# motor_controller.net
KiCad netlist of a schematic drawn in EAGLE
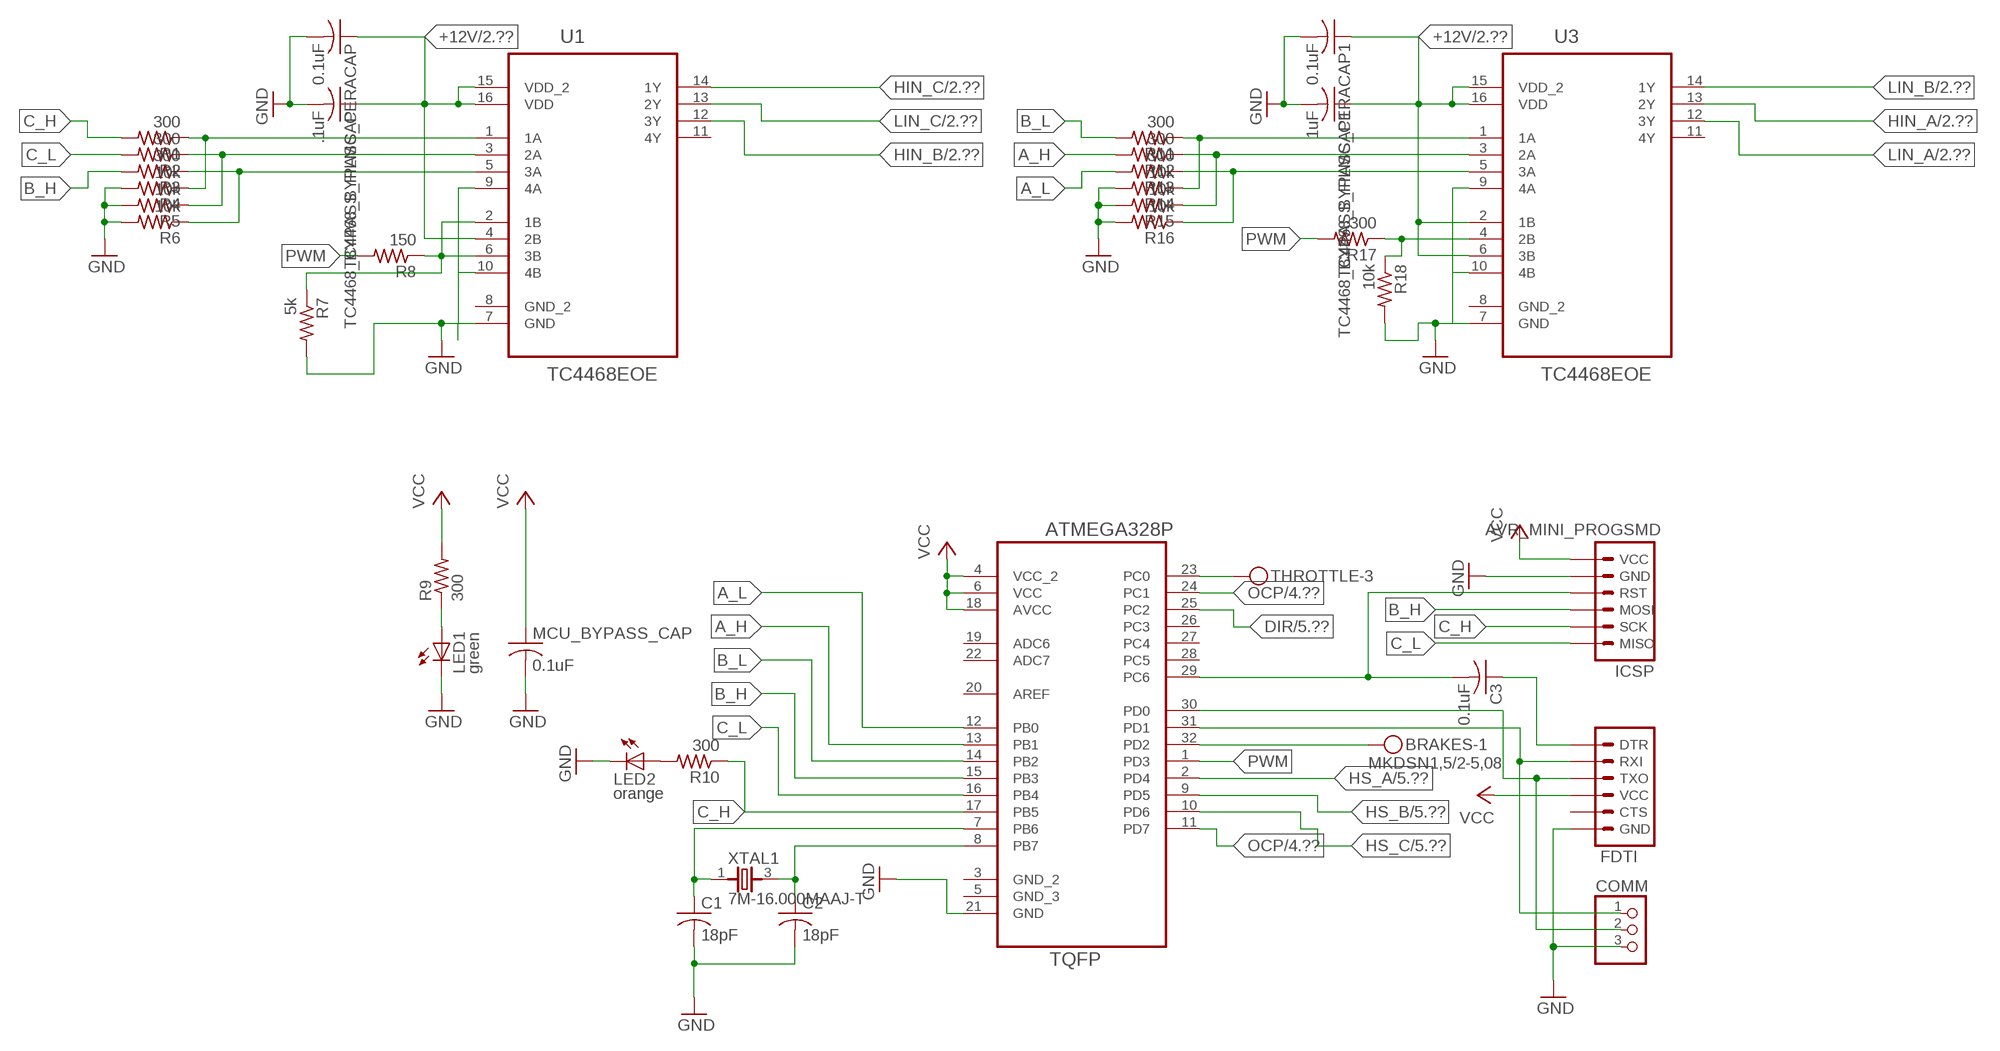
[diagram p0: schematic, sheet 1]
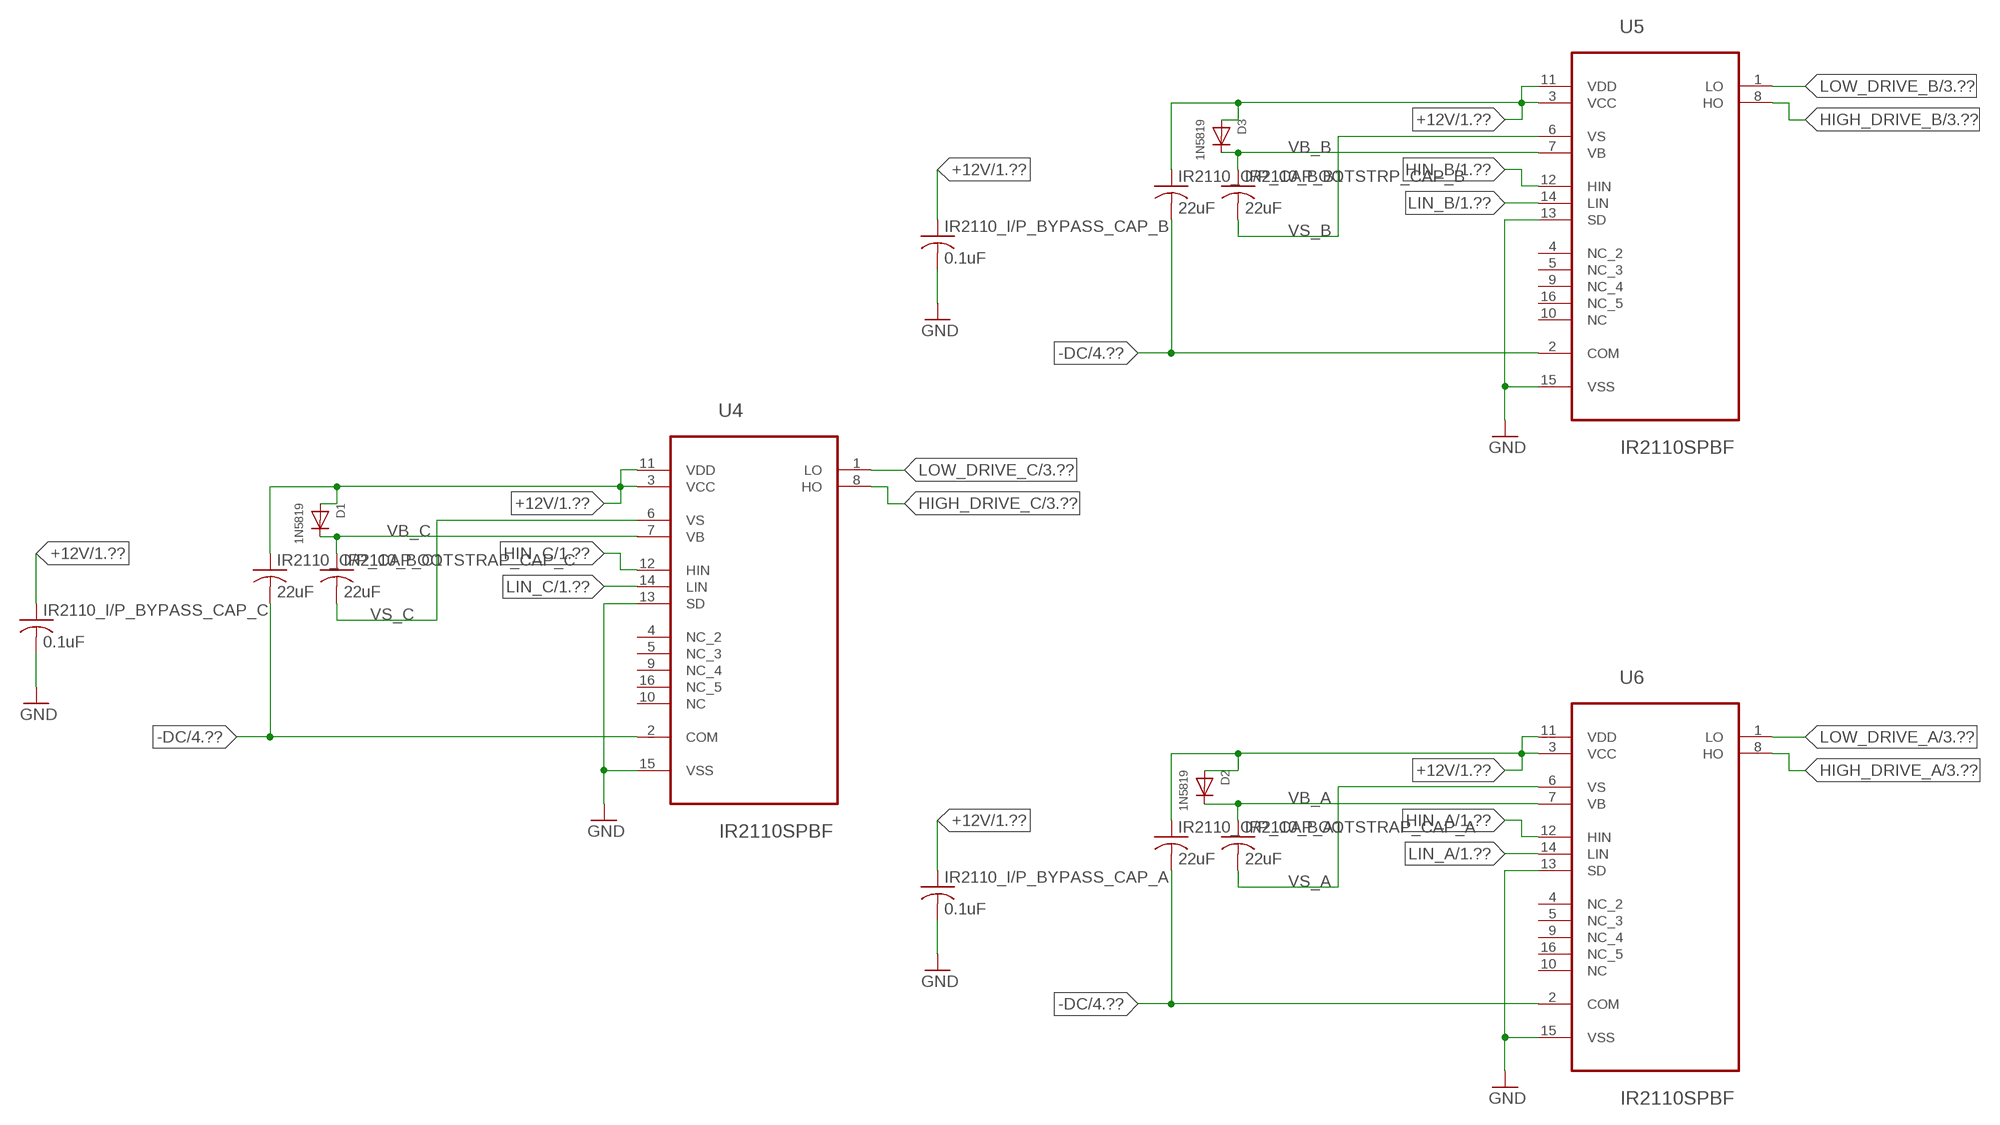
[diagram p1: schematic, sheet 2]
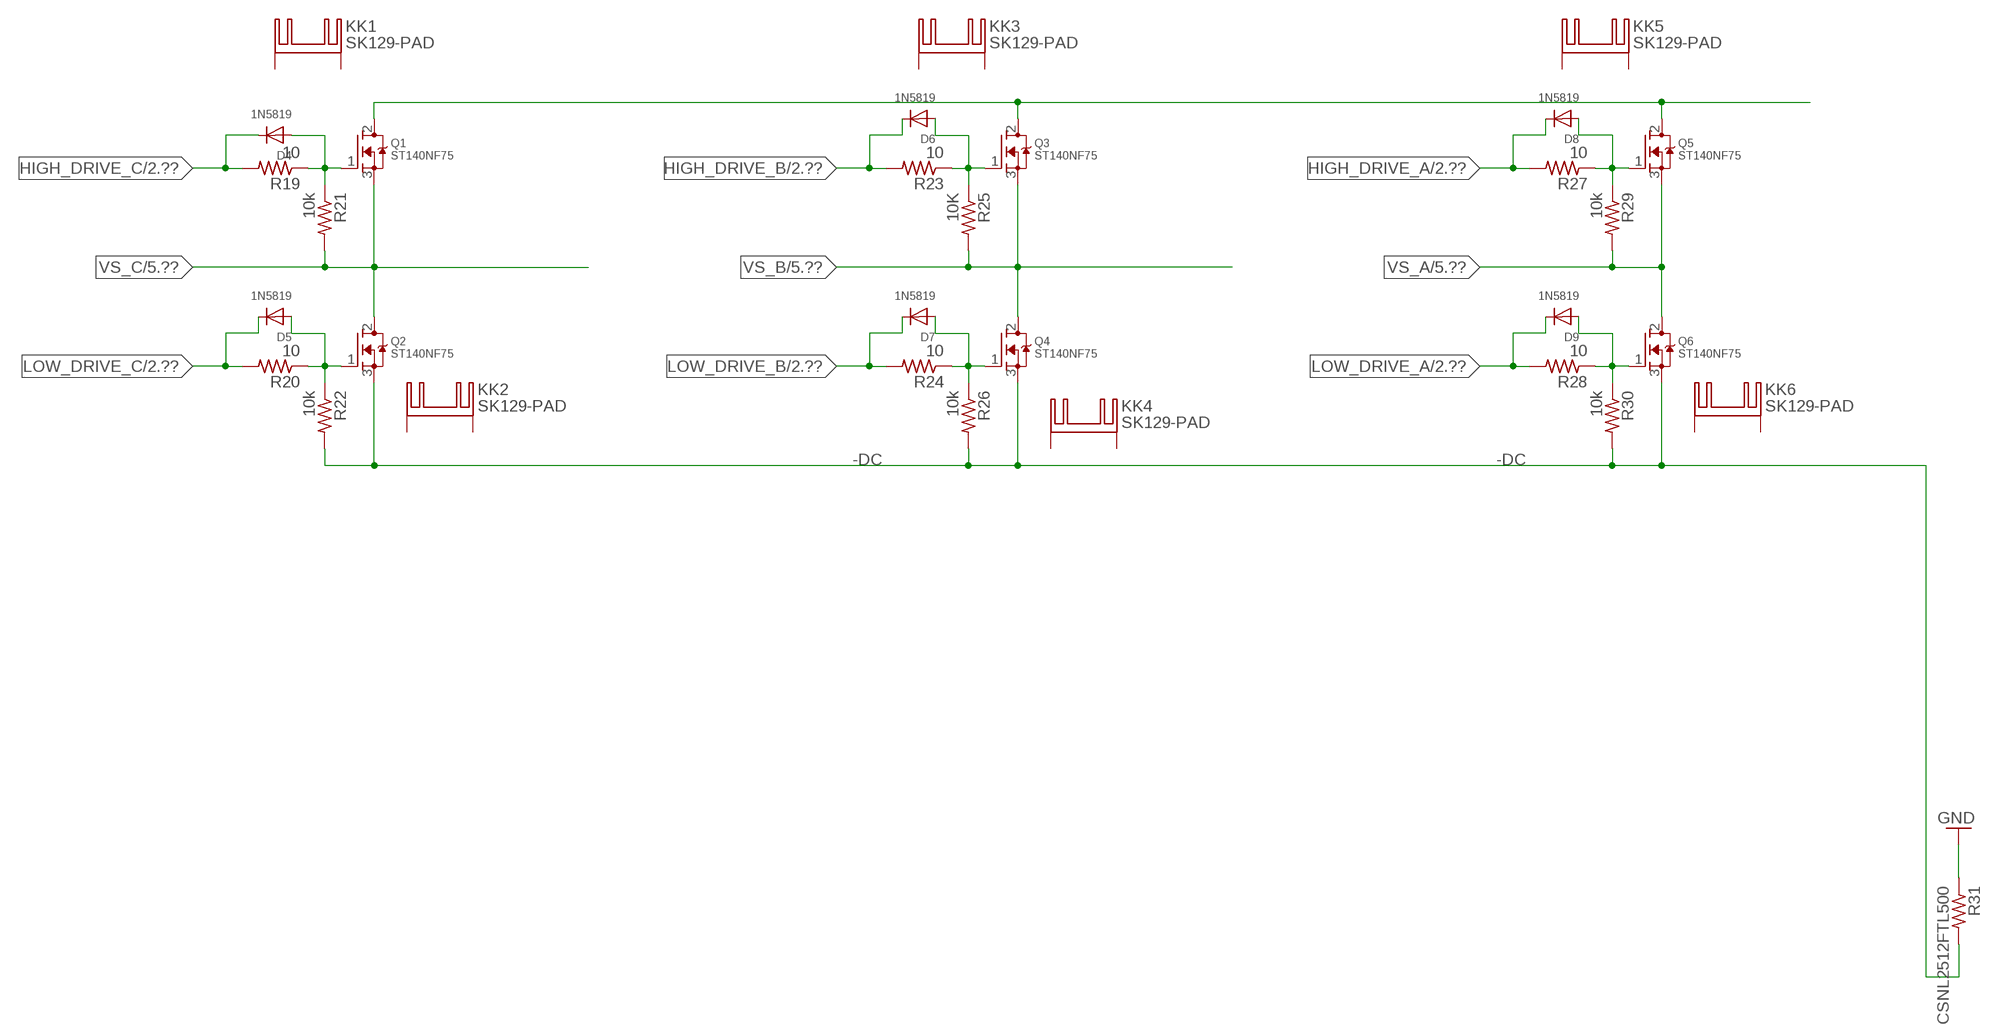
[diagram p2: schematic, sheet 3]
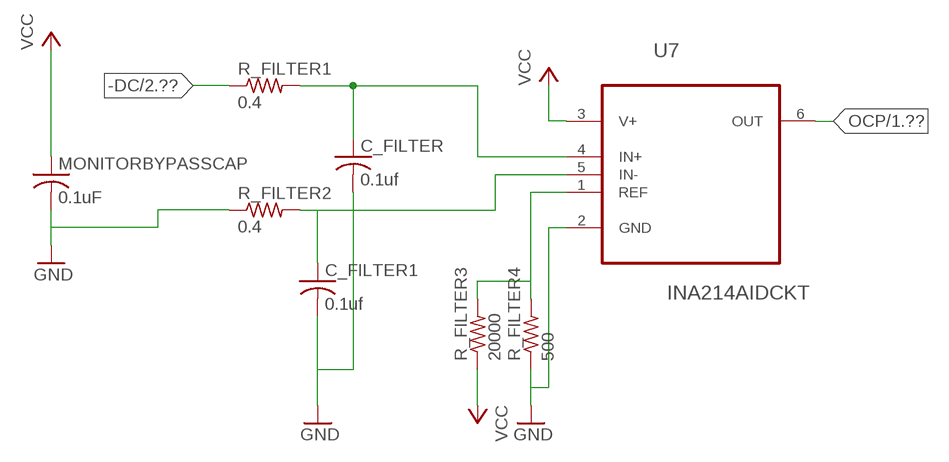
[diagram p3: schematic, sheet 4]
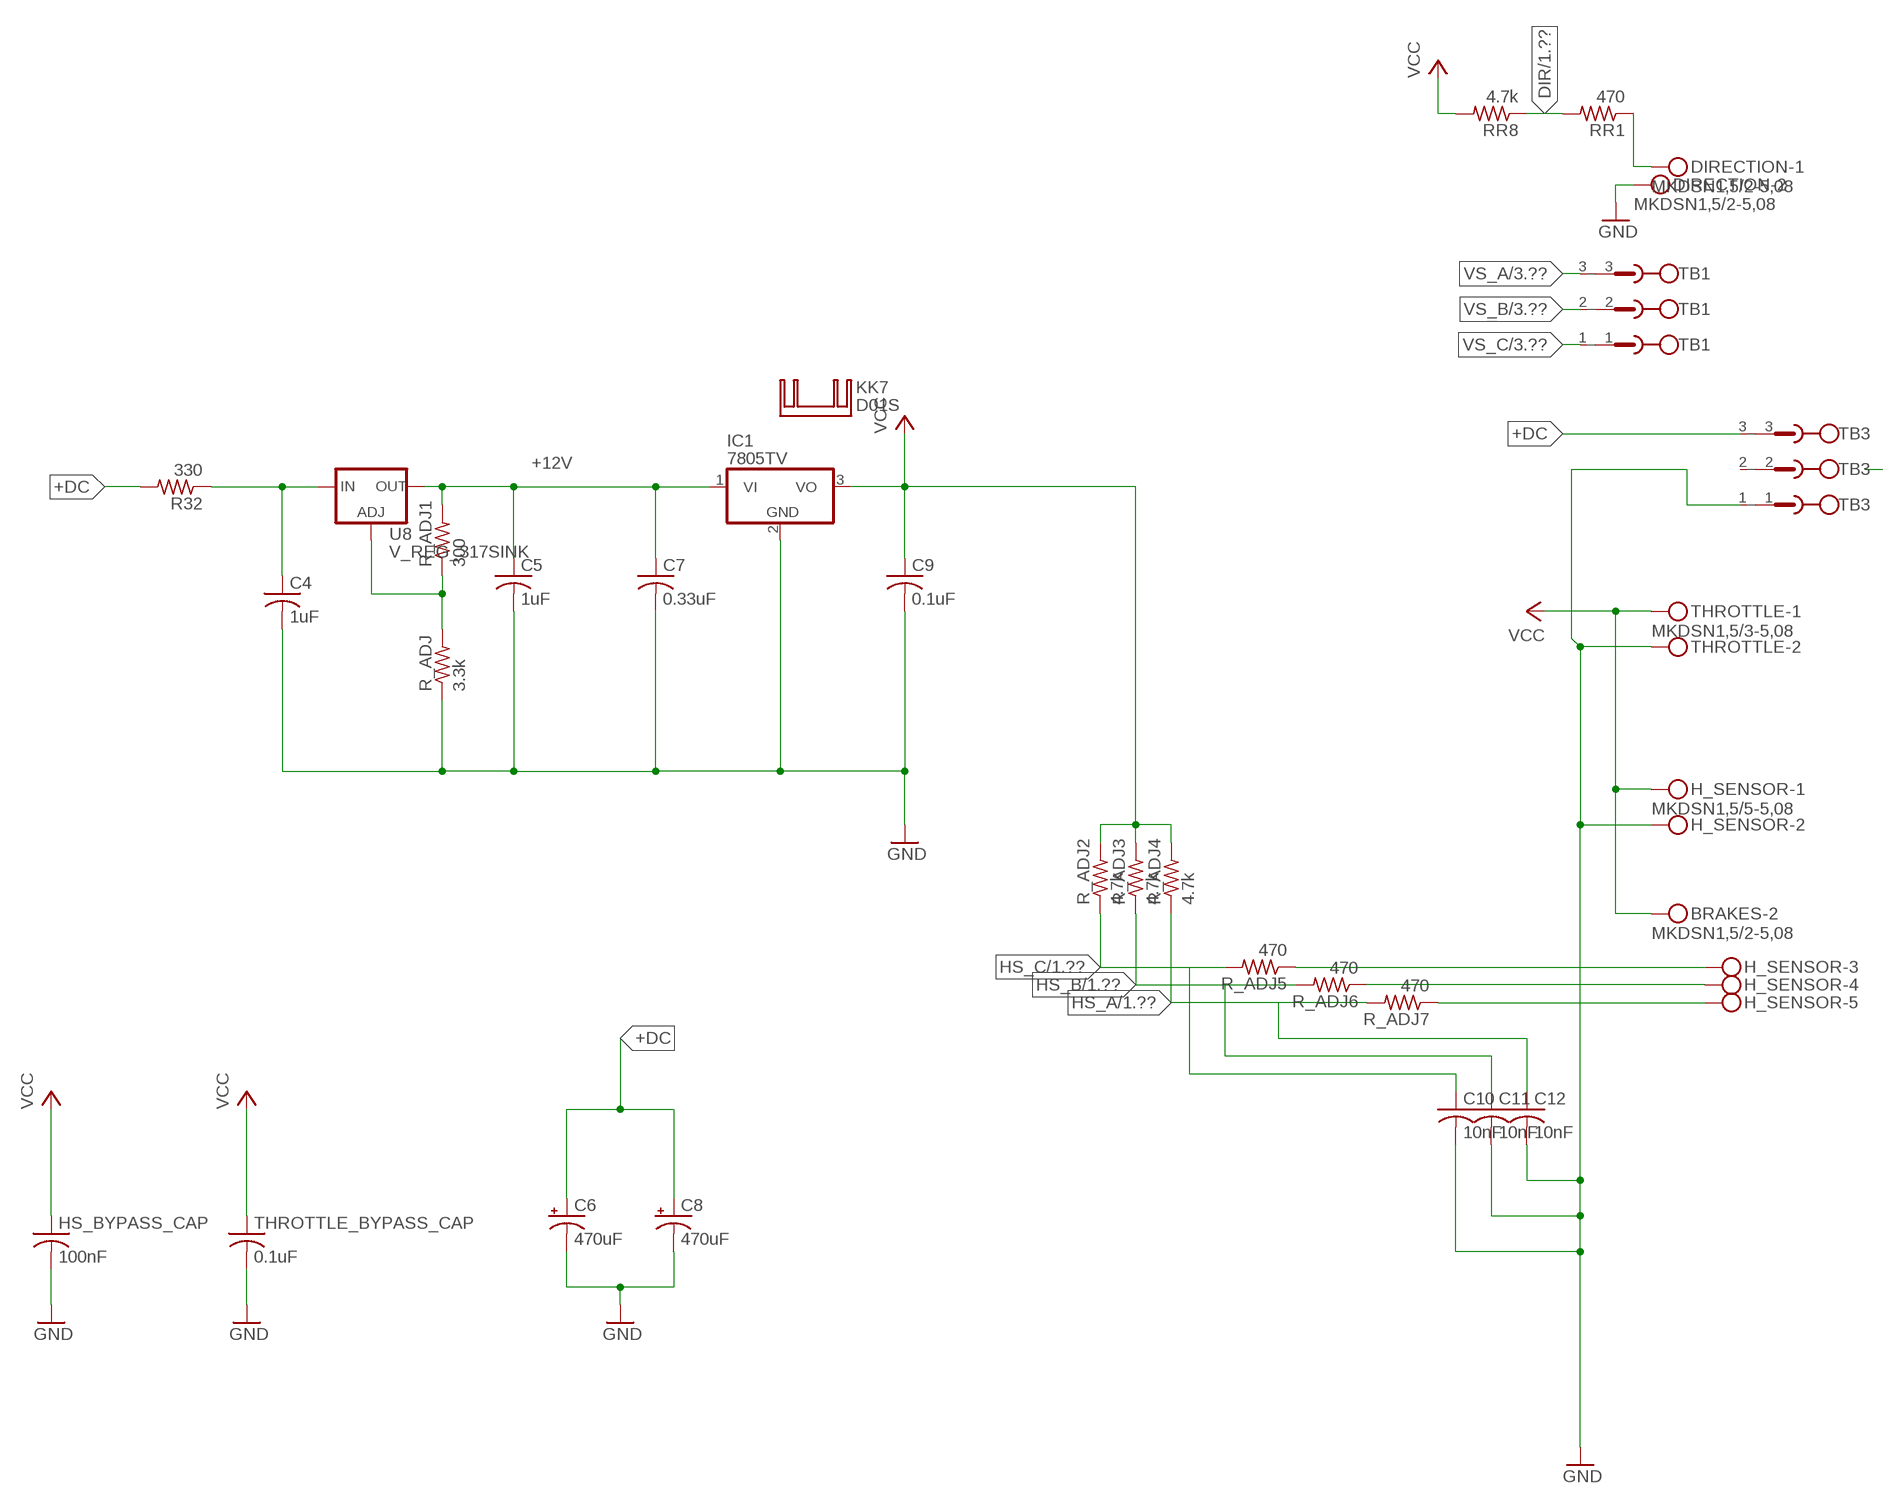
[diagram p4: schematic, sheet 5]

(export (version "E")
  (design (tool "Eeschema 10.0.6"))
  (components
    (comp (ref "BRAKES")
      (value "MKDSN1,5/2-5,08")
      (footprint "eagle-import:MKDSN1,5_2-5,08")
      (fields (field (name "MPN") "MKDSN 1,5/2-5.08"))
      (libsource (lib "eagle-import") (part "MKDSN1,5/2-5,08"))
    )
    (comp (ref "C1")
      (value "18pF")
      (footprint "eagle-import:C0805")
      (libsource (lib "eagle-import") (part "C-USC0805"))
    )
    (comp (ref "C2")
      (value "18pF")
      (footprint "eagle-import:C0805")
      (libsource (lib "eagle-import") (part "C-USC0805"))
    )
    (comp (ref "C3")
      (value "0.1uF")
      (footprint "eagle-import:C0805")
      (libsource (lib "eagle-import") (part "C-USC0805"))
    )
    (comp (ref "COMM")
      (value "PINHD-1X3")
      (footprint "eagle-import:1X03")
      (libsource (lib "eagle-import") (part "PINHD-1X3"))
    )
    (comp (ref "FDTI")
      (value "ARDUINO_SERIAL_PROGRAMLONGPADS")
      (footprint "eagle-import:1X06_LONGPADS")
      (libsource (lib "eagle-import") (part "ARDUINO_SERIAL_PROGRAMLONGPADS"))
    )
    (comp (ref "ICSP")
      (value "AVR_MINI_PROGSMD")
      (footprint "eagle-import:AVR_MINI_PROG")
      (libsource (lib "eagle-import") (part "AVR_MINI_PROGSMD"))
    )
    (comp (ref "LED1")
      (value "green")
      (footprint "eagle-import:CHIPLED_0805")
      (libsource (lib "eagle-import") (part "LEDCHIPLED_0805"))
    )
    (comp (ref "LED2")
      (value "orange")
      (footprint "eagle-import:CHIPLED_0805")
      (libsource (lib "eagle-import") (part "LEDCHIPLED_0805"))
    )
    (comp (ref "MCU_BYPASS_CAP")
      (value "0.1uF")
      (footprint "eagle-import:C0805")
      (libsource (lib "eagle-import") (part "C-USC0805"))
    )
    (comp (ref "R1")
      (value "300")
      (footprint "eagle-import:R0805")
      (libsource (lib "eagle-import") (part "R-US_R0805"))
    )
    (comp (ref "R2")
      (value "300")
      (footprint "eagle-import:R0805")
      (libsource (lib "eagle-import") (part "R-US_R0805"))
    )
    (comp (ref "R3")
      (value "300")
      (footprint "eagle-import:R0805")
      (libsource (lib "eagle-import") (part "R-US_R0805"))
    )
    (comp (ref "R4")
      (value "10k")
      (footprint "eagle-import:R0805")
      (libsource (lib "eagle-import") (part "R-US_R0805"))
    )
    (comp (ref "R5")
      (value "10k")
      (footprint "eagle-import:R0805")
      (libsource (lib "eagle-import") (part "R-US_R0805"))
    )
    (comp (ref "R6")
      (value "10k")
      (footprint "eagle-import:R0805")
      (libsource (lib "eagle-import") (part "R-US_R0805"))
    )
    (comp (ref "R7")
      (value "5k")
      (footprint "eagle-import:R0805")
      (libsource (lib "eagle-import") (part "R-US_R0805"))
    )
    (comp (ref "R8")
      (value "150")
      (footprint "eagle-import:R0805")
      (libsource (lib "eagle-import") (part "R-US_R0805"))
    )
    (comp (ref "R9")
      (value "300")
      (footprint "eagle-import:R0805")
      (libsource (lib "eagle-import") (part "R-US_R0805"))
    )
    (comp (ref "R10")
      (value "300")
      (footprint "eagle-import:R0805")
      (libsource (lib "eagle-import") (part "R-US_R0805"))
    )
    (comp (ref "R11")
      (value "300")
      (footprint "eagle-import:R0805")
      (libsource (lib "eagle-import") (part "R-US_R0805"))
    )
    (comp (ref "R12")
      (value "300")
      (footprint "eagle-import:R0805")
      (libsource (lib "eagle-import") (part "R-US_R0805"))
    )
    (comp (ref "R13")
      (value "300")
      (footprint "eagle-import:R0805")
      (libsource (lib "eagle-import") (part "R-US_R0805"))
    )
    (comp (ref "R14")
      (value "10k")
      (footprint "eagle-import:R0805")
      (libsource (lib "eagle-import") (part "R-US_R0805"))
    )
    (comp (ref "R15")
      (value "10k")
      (footprint "eagle-import:R0805")
      (libsource (lib "eagle-import") (part "R-US_R0805"))
    )
    (comp (ref "R16")
      (value "10k")
      (footprint "eagle-import:R0805")
      (libsource (lib "eagle-import") (part "R-US_R0805"))
    )
    (comp (ref "R17")
      (value "300")
      (footprint "eagle-import:R0805")
      (libsource (lib "eagle-import") (part "R-US_R0805"))
    )
    (comp (ref "R18")
      (value "10k")
      (footprint "eagle-import:R0805")
      (libsource (lib "eagle-import") (part "R-US_R0805"))
    )
    (comp (ref "TC4468_BYPASS_CERACAP")
      (value "0.1uF")
      (footprint "eagle-import:C0805")
      (libsource (lib "eagle-import") (part "C-USC0805"))
    )
    (comp (ref "TC4468_BYPASS_CERACAP1")
      (value "0.1uF")
      (footprint "eagle-import:C0805")
      (libsource (lib "eagle-import") (part "C-USC0805"))
    )
    (comp (ref "TC4468_BYPASS_FILMCAP")
      (value ".1uF")
      (footprint "eagle-import:C0805")
      (libsource (lib "eagle-import") (part "C-USC0805"))
    )
    (comp (ref "TC4468_BYPASS_FILMCAP1")
      (value "1uF")
      (footprint "eagle-import:C0805")
      (libsource (lib "eagle-import") (part "C-USC0805"))
    )
    (comp (ref "THROTTLE")
      (value "MKDSN1,5/3-5,08")
      (footprint "eagle-import:MKDSN1,5_3-5,08")
      (fields (field (name "MPN") "SMKDSN1,5/3-5,08"))
      (libsource (lib "eagle-import") (part "MKDSN1,5/3-5,08"))
    )
    (comp (ref "U1")
      (value "TC4468EOE")
      (footprint "eagle-import:SOIC127P1030X265-16N")
      (libsource (lib "eagle-import") (part "TC4468EOE"))
    )
    (comp (ref "U2")
      (value "ATMEGA328P-AU")
      (footprint "eagle-import:QFP80P900X900X120-32N")
      (libsource (lib "eagle-import") (part "ATMEGA328P-AU"))
    )
    (comp (ref "U3")
      (value "TC4468EOE")
      (footprint "eagle-import:SOIC127P1030X265-16N")
      (libsource (lib "eagle-import") (part "TC4468EOE"))
    )
    (comp (ref "XTAL1")
      (value "7M-16.000MAAJ-T")
      (footprint "eagle-import:TXC_7M-16.000MAAJ-T")
      (fields (field (name "MPN") "7M-16.000MAAJ-T "))
      (libsource (lib "eagle-import") (part "7M-16.000MAAJ-T"))
    )
    (comp (ref "D1")
      (value "1N5819")
      (footprint "eagle-import:SOD-123")
      (libsource (lib "eagle-import") (part "DIODESOD-123"))
    )
    (comp (ref "D2")
      (value "1N5819")
      (footprint "eagle-import:SOD-123")
      (libsource (lib "eagle-import") (part "DIODESOD-123"))
    )
    (comp (ref "D3")
      (value "1N5819")
      (footprint "eagle-import:SOD-123")
      (libsource (lib "eagle-import") (part "DIODESOD-123"))
    )
    (comp (ref "IR2110_BOOTSTRAP_CAP_A")
      (value "22uF")
      (footprint "eagle-import:C2917")
      (libsource (lib "eagle-import") (part "C2917"))
    )
    (comp (ref "IR2110_BOOTSTRAP_CAP_C")
      (value "22uF")
      (footprint "eagle-import:C2917")
      (libsource (lib "eagle-import") (part "C2917"))
    )
    (comp (ref "IR2110_BOOTSTRP_CAP_B")
      (value "22uF")
      (footprint "eagle-import:C2917")
      (libsource (lib "eagle-import") (part "C2917"))
    )
    (comp (ref "IR2110_I/P_BYPASS_CAP_A")
      (value "0.1uF")
      (footprint "eagle-import:C0805")
      (libsource (lib "eagle-import") (part "C-USC0805"))
    )
    (comp (ref "IR2110_I/P_BYPASS_CAP_B")
      (value "0.1uF")
      (footprint "eagle-import:C0805")
      (libsource (lib "eagle-import") (part "C-USC0805"))
    )
    (comp (ref "IR2110_I/P_BYPASS_CAP_C")
      (value "0.1uF")
      (footprint "eagle-import:C0805")
      (libsource (lib "eagle-import") (part "C-USC0805"))
    )
    (comp (ref "IR2110_O/P_CAP_A1")
      (value "22uF")
      (footprint "eagle-import:C2917")
      (libsource (lib "eagle-import") (part "C2917"))
    )
    (comp (ref "IR2110_O/P_CAP_B1")
      (value "22uF")
      (footprint "eagle-import:C2917")
      (libsource (lib "eagle-import") (part "C2917"))
    )
    (comp (ref "IR2110_O/P_CAP_C1")
      (value "22uF")
      (footprint "eagle-import:C2917")
      (libsource (lib "eagle-import") (part "C2917"))
    )
    (comp (ref "U4")
      (value "IR2110SPBF")
      (footprint "eagle-import:SOIC127P1030X265-16N")
      (libsource (lib "eagle-import") (part "IR2110SPBF"))
    )
    (comp (ref "U5")
      (value "IR2110SPBF")
      (footprint "eagle-import:SOIC127P1030X265-16N")
      (libsource (lib "eagle-import") (part "IR2110SPBF"))
    )
    (comp (ref "U6")
      (value "IR2110SPBF")
      (footprint "eagle-import:SOIC127P1030X265-16N")
      (libsource (lib "eagle-import") (part "IR2110SPBF"))
    )
    (comp (ref "C4")
      (value "1uF")
      (footprint "eagle-import:C0805")
      (libsource (lib "eagle-import") (part "C-USC0805"))
    )
    (comp (ref "C5")
      (value "1uF")
      (footprint "eagle-import:C0805")
      (libsource (lib "eagle-import") (part "C-USC0805"))
    )
    (comp (ref "C6")
      (value "470uF")
      (footprint "eagle-import:CPOL-RADIAL-1000UF-25V")
      (libsource (lib "eagle-import") (part "1000UF-25V(PTH)"))
    )
    (comp (ref "C7")
      (value "0.33uF")
      (footprint "eagle-import:C0805")
      (libsource (lib "eagle-import") (part "C-USC0805"))
    )
    (comp (ref "C8")
      (value "470uF")
      (footprint "eagle-import:CPOL-RADIAL-1000UF-25V")
      (libsource (lib "eagle-import") (part "1000UF-25V(PTH)"))
    )
    (comp (ref "C9")
      (value "0.1uF")
      (footprint "eagle-import:C0805")
      (libsource (lib "eagle-import") (part "C-USC0805"))
    )
    (comp (ref "C10")
      (value "10nF")
      (footprint "eagle-import:C0805")
      (libsource (lib "eagle-import") (part "C-USC0805"))
    )
    (comp (ref "C11")
      (value "10nF")
      (footprint "eagle-import:C0805")
      (libsource (lib "eagle-import") (part "C-USC0805"))
    )
    (comp (ref "C12")
      (value "10nF")
      (footprint "eagle-import:C0805")
      (libsource (lib "eagle-import") (part "C-USC0805"))
    )
    (comp (ref "DIRECTION")
      (value "MKDSN1,5/2-5,08")
      (footprint "eagle-import:MKDSN1,5_2-5,08")
      (fields (field (name "MPN") "MKDSN 1,5/2-5.08"))
      (libsource (lib "eagle-import") (part "MKDSN1,5/2-5,08"))
    )
    (comp (ref "HS_BYPASS_CAP")
      (value "100nF")
      (footprint "eagle-import:C0805")
      (libsource (lib "eagle-import") (part "C-USC0805"))
    )
    (comp (ref "H_SENSOR")
      (value "MKDSN1,5/5-5,08")
      (footprint "eagle-import:MKDSN1,5_5-5,08")
      (fields (field (name "MPN") "SMKDSN1,5/5-5,08"))
      (libsource (lib "eagle-import") (part "MKDSN1,5/5-5,08"))
    )
    (comp (ref "IC1")
      (value "7805TV")
      (footprint "eagle-import:TO220V")
      (libsource (lib "eagle-import") (part "78TV05"))
    )
    (comp (ref "KK7")
      (value "D01S")
      (footprint "eagle-import:D01S")
      (libsource (lib "eagle-import") (part "D01S"))
    )
    (comp (ref "R32")
      (value "330")
      (footprint "eagle-import:R2512")
      (libsource (lib "eagle-import") (part "resistor_R-US_R2512"))
    )
    (comp (ref "RR1")
      (value "470")
      (footprint "eagle-import:R0805")
      (libsource (lib "eagle-import") (part "R-US_R0805"))
    )
    (comp (ref "RR8")
      (value "4.7k")
      (footprint "eagle-import:R0805")
      (libsource (lib "eagle-import") (part "R-US_R0805"))
    )
    (comp (ref "R_ADJ")
      (value "3.3k")
      (footprint "eagle-import:R0805")
      (libsource (lib "eagle-import") (part "R-US_R0805"))
    )
    (comp (ref "R_ADJ1")
      (value "300")
      (footprint "eagle-import:R0805")
      (libsource (lib "eagle-import") (part "R-US_R0805"))
    )
    (comp (ref "R_ADJ2")
      (value "4.7k")
      (footprint "eagle-import:R0805")
      (libsource (lib "eagle-import") (part "R-US_R0805"))
    )
    (comp (ref "R_ADJ3")
      (value "4.7k")
      (footprint "eagle-import:R0805")
      (libsource (lib "eagle-import") (part "R-US_R0805"))
    )
    (comp (ref "R_ADJ4")
      (value "4.7k")
      (footprint "eagle-import:R0805")
      (libsource (lib "eagle-import") (part "R-US_R0805"))
    )
    (comp (ref "R_ADJ5")
      (value "470")
      (footprint "eagle-import:R0805")
      (libsource (lib "eagle-import") (part "R-US_R0805"))
    )
    (comp (ref "R_ADJ6")
      (value "470")
      (footprint "eagle-import:R0805")
      (libsource (lib "eagle-import") (part "R-US_R0805"))
    )
    (comp (ref "R_ADJ7")
      (value "470")
      (footprint "eagle-import:R0805")
      (libsource (lib "eagle-import") (part "R-US_R0805"))
    )
    (comp (ref "TB1")
      (value "MKDSP 10N/ 3-10,16")
      (footprint "eagle-import:MKDSP10N_3-10,16")
      (libsource (lib "eagle-import") (part "MKDSP10N/3-10,16"))
    )
    (comp (ref "TB3")
      (value "MKDSP 10N/ 3-10,16")
      (footprint "eagle-import:MKDSP10N_3-10,16")
      (libsource (lib "eagle-import") (part "MKDSP10N/3-10,16"))
    )
    (comp (ref "THROTTLE_BYPASS_CAP")
      (value "0.1uF")
      (footprint "eagle-import:C0805")
      (libsource (lib "eagle-import") (part "C-USC0805"))
    )
    (comp (ref "U8")
      (value "V_REG_317SINK")
      (footprint "eagle-import:TO220-ADJ")
      (libsource (lib "eagle-import") (part "V_REG_317SINK"))
    )
    (comp (ref "D4")
      (value "1N5819")
      (footprint "eagle-import:SOD-123")
      (libsource (lib "eagle-import") (part "DIODESOD-123"))
    )
    (comp (ref "D5")
      (value "1N5819")
      (footprint "eagle-import:SOD-123")
      (libsource (lib "eagle-import") (part "DIODESOD-123"))
    )
    (comp (ref "D6")
      (value "1N5819")
      (footprint "eagle-import:SOD-123")
      (libsource (lib "eagle-import") (part "DIODESOD-123"))
    )
    (comp (ref "D7")
      (value "1N5819")
      (footprint "eagle-import:SOD-123")
      (libsource (lib "eagle-import") (part "DIODESOD-123"))
    )
    (comp (ref "D8")
      (value "1N5819")
      (footprint "eagle-import:SOD-123")
      (libsource (lib "eagle-import") (part "DIODESOD-123"))
    )
    (comp (ref "D9")
      (value "1N5819")
      (footprint "eagle-import:SOD-123")
      (libsource (lib "eagle-import") (part "DIODESOD-123"))
    )
    (comp (ref "KK1")
      (value "SK129-PAD")
      (footprint "eagle-import:SK129")
      (libsource (lib "eagle-import") (part "SK129-PAD"))
    )
    (comp (ref "KK2")
      (value "SK129-PAD")
      (footprint "eagle-import:SK129")
      (libsource (lib "eagle-import") (part "SK129-PAD"))
    )
    (comp (ref "KK3")
      (value "SK129-PAD")
      (footprint "eagle-import:SK129")
      (libsource (lib "eagle-import") (part "SK129-PAD"))
    )
    (comp (ref "KK4")
      (value "SK129-PAD")
      (footprint "eagle-import:SK129")
      (libsource (lib "eagle-import") (part "SK129-PAD"))
    )
    (comp (ref "KK5")
      (value "SK129-PAD")
      (footprint "eagle-import:SK129")
      (libsource (lib "eagle-import") (part "SK129-PAD"))
    )
    (comp (ref "KK6")
      (value "SK129-PAD")
      (footprint "eagle-import:SK129")
      (libsource (lib "eagle-import") (part "SK129-PAD"))
    )
    (comp (ref "Q1")
      (value "ST140NF75")
      (footprint "eagle-import:TO220V")
      (libsource (lib "eagle-import") (part "MOSFET-NGDS_TO220V"))
    )
    (comp (ref "Q2")
      (value "ST140NF75")
      (footprint "eagle-import:TO220V")
      (libsource (lib "eagle-import") (part "MOSFET-NGDS_TO220V"))
    )
    (comp (ref "Q3")
      (value "ST140NF75")
      (footprint "eagle-import:TO220V")
      (libsource (lib "eagle-import") (part "MOSFET-NGDS_TO220V"))
    )
    (comp (ref "Q4")
      (value "ST140NF75")
      (footprint "eagle-import:TO220V")
      (libsource (lib "eagle-import") (part "MOSFET-NGDS_TO220V"))
    )
    (comp (ref "Q5")
      (value "ST140NF75")
      (footprint "eagle-import:TO220V")
      (libsource (lib "eagle-import") (part "MOSFET-NGDS_TO220V"))
    )
    (comp (ref "Q6")
      (value "ST140NF75")
      (footprint "eagle-import:TO220V")
      (libsource (lib "eagle-import") (part "MOSFET-NGDS_TO220V"))
    )
    (comp (ref "R19")
      (value "10")
      (footprint "eagle-import:R0805")
      (libsource (lib "eagle-import") (part "R-US_R0805"))
    )
    (comp (ref "R20")
      (value "10")
      (footprint "eagle-import:R0805")
      (libsource (lib "eagle-import") (part "R-US_R0805"))
    )
    (comp (ref "R21")
      (value "10k")
      (footprint "eagle-import:R0805")
      (libsource (lib "eagle-import") (part "R-US_R0805"))
    )
    (comp (ref "R22")
      (value "10k")
      (footprint "eagle-import:R0805")
      (libsource (lib "eagle-import") (part "R-US_R0805"))
    )
    (comp (ref "R23")
      (value "10")
      (footprint "eagle-import:R0805")
      (libsource (lib "eagle-import") (part "R-US_R0805"))
    )
    (comp (ref "R24")
      (value "10")
      (footprint "eagle-import:R0805")
      (libsource (lib "eagle-import") (part "R-US_R0805"))
    )
    (comp (ref "R25")
      (value "10K")
      (footprint "eagle-import:R0805")
      (libsource (lib "eagle-import") (part "R-US_R0805"))
    )
    (comp (ref "R26")
      (value "10k")
      (footprint "eagle-import:R0805")
      (libsource (lib "eagle-import") (part "R-US_R0805"))
    )
    (comp (ref "R27")
      (value "10")
      (footprint "eagle-import:R0805")
      (libsource (lib "eagle-import") (part "R-US_R0805"))
    )
    (comp (ref "R28")
      (value "10")
      (footprint "eagle-import:R0805")
      (libsource (lib "eagle-import") (part "R-US_R0805"))
    )
    (comp (ref "R29")
      (value "10k")
      (footprint "eagle-import:R0805")
      (libsource (lib "eagle-import") (part "R-US_R0805"))
    )
    (comp (ref "R30")
      (value "10k")
      (footprint "eagle-import:R0805")
      (libsource (lib "eagle-import") (part "R-US_R0805"))
    )
    (comp (ref "R31")
      (value "CSNL2512FTL500")
      (footprint "eagle-import:R2512")
      (libsource (lib "eagle-import") (part "R-US_R2512"))
    )
    (comp (ref "C_FILTER")
      (value "0.1uf")
      (footprint "eagle-import:C0603")
      (libsource (lib "eagle-import") (part "resistor_C-USC0603"))
    )
    (comp (ref "C_FILTER1")
      (value "0.1uf")
      (footprint "eagle-import:C0603")
      (libsource (lib "eagle-import") (part "resistor_C-USC0603"))
    )
    (comp (ref "MONITORBYPASSCAP")
      (value "0.1uF")
      (footprint "eagle-import:C0805")
      (libsource (lib "eagle-import") (part "C-USC0805"))
    )
    (comp (ref "R_FILTER1")
      (value "0.4")
      (footprint "eagle-import:R0603")
      (libsource (lib "eagle-import") (part "resistor_R-US_R0603"))
    )
    (comp (ref "R_FILTER2")
      (value "0.4")
      (footprint "eagle-import:R0603")
      (libsource (lib "eagle-import") (part "resistor_R-US_R0603"))
    )
    (comp (ref "R_FILTER3")
      (value "20000")
      (footprint "eagle-import:R0805")
      (libsource (lib "eagle-import") (part "R-US_R0805"))
    )
    (comp (ref "R_FILTER4")
      (value "500")
      (footprint "eagle-import:R0805")
      (libsource (lib "eagle-import") (part "R-US_R0805"))
    )
    (comp (ref "U7")
      (value "INA214AIDCKT")
      (footprint "eagle-import:SOT65P210X110-6N")
      (libsource (lib "eagle-import") (part "INA214AIDCKT"))
    )
  )
  (nets
    (net (code "1") (name "+12V") (class "Default")
      (node (ref "C5") (pin "1") (pinfunction "1_1") (pintype "passive"))
      (node (ref "C7") (pin "1") (pinfunction "1_1") (pintype "passive"))
      (node (ref "D1") (pin "A") (pinfunction "A_A") (pintype "passive"))
      (node (ref "D2") (pin "A") (pinfunction "A_A") (pintype "passive"))
      (node (ref "D3") (pin "A") (pinfunction "A_A") (pintype "passive"))
      (node (ref "IC1") (pin "1") (pinfunction "VI_1") (pintype "input"))
      (node (ref "IR2110_I/P_BYPASS_CAP_A") (pin "1") (pinfunction "1_1") (pintype "passive"))
      (node (ref "IR2110_I/P_BYPASS_CAP_B") (pin "1") (pinfunction "1_1") (pintype "passive"))
      (node (ref "IR2110_I/P_BYPASS_CAP_C") (pin "1") (pinfunction "1_1") (pintype "passive"))
      (node (ref "IR2110_O/P_CAP_A1") (pin "P$1") (pinfunction "1_P$1") (pintype "passive"))
      (node (ref "IR2110_O/P_CAP_B1") (pin "P$1") (pinfunction "1_P$1") (pintype "passive"))
      (node (ref "IR2110_O/P_CAP_C1") (pin "P$1") (pinfunction "1_P$1") (pintype "passive"))
      (node (ref "R_ADJ1") (pin "2") (pinfunction "2_2") (pintype "passive"))
      (node (ref "TC4468_BYPASS_CERACAP") (pin "1") (pinfunction "1_1") (pintype "passive"))
      (node (ref "TC4468_BYPASS_CERACAP1") (pin "1") (pinfunction "1_1") (pintype "passive"))
      (node (ref "TC4468_BYPASS_FILMCAP") (pin "1") (pinfunction "1_1") (pintype "passive"))
      (node (ref "TC4468_BYPASS_FILMCAP1") (pin "1") (pinfunction "1_1") (pintype "passive"))
      (node (ref "U1") (pin "15") (pinfunction "VDD_2_15") (pintype "power_in"))
      (node (ref "U1") (pin "16") (pinfunction "VDD_16") (pintype "power_in"))
      (node (ref "U1") (pin "4") (pinfunction "2B_4") (pintype "input"))
      (node (ref "U3") (pin "15") (pinfunction "VDD_2_15") (pintype "power_in"))
      (node (ref "U3") (pin "16") (pinfunction "VDD_16") (pintype "power_in"))
      (node (ref "U3") (pin "2") (pinfunction "1B_2") (pintype "input"))
      (node (ref "U3") (pin "6") (pinfunction "3B_6") (pintype "input"))
      (node (ref "U4") (pin "11") (pinfunction "VDD_11") (pintype "power_in"))
      (node (ref "U4") (pin "3") (pinfunction "VCC_3") (pintype "power_in"))
      (node (ref "U5") (pin "11") (pinfunction "VDD_11") (pintype "power_in"))
      (node (ref "U5") (pin "3") (pinfunction "VCC_3") (pintype "power_in"))
      (node (ref "U6") (pin "11") (pinfunction "VDD_11") (pintype "power_in"))
      (node (ref "U6") (pin "3") (pinfunction "VCC_3") (pintype "power_in"))
      (node (ref "U8") (pin "OUT") (pinfunction "OUT_OUT") (pintype "output"))
    )
    (net (code "2") (name "+DC") (class "Default")
      (node (ref "C6") (pin "+") (pinfunction "+_+") (pintype "passive"))
      (node (ref "C8") (pin "+") (pinfunction "+_+") (pintype "passive"))
      (node (ref "Q1") (pin "2") (pinfunction "D_2") (pintype "bidirectional"))
      (node (ref "Q3") (pin "2") (pinfunction "D_2") (pintype "bidirectional"))
      (node (ref "Q5") (pin "2") (pinfunction "D_2") (pintype "bidirectional"))
      (node (ref "R32") (pin "2") (pinfunction "2_2") (pintype "passive"))
      (node (ref "TB3") (pin "3_") (pinfunction "6_3_") (pintype "passive"))
    )
    (net (code "3") (name "-DC") (class "Default")
      (node (ref "IR2110_O/P_CAP_A1") (pin "P$2") (pinfunction "2_P$2") (pintype "passive"))
      (node (ref "IR2110_O/P_CAP_B1") (pin "P$2") (pinfunction "2_P$2") (pintype "passive"))
      (node (ref "IR2110_O/P_CAP_C1") (pin "P$2") (pinfunction "2_P$2") (pintype "passive"))
      (node (ref "Q2") (pin "3") (pinfunction "S_3") (pintype "bidirectional"))
      (node (ref "Q4") (pin "3") (pinfunction "S_3") (pintype "bidirectional"))
      (node (ref "Q6") (pin "3") (pinfunction "S_3") (pintype "bidirectional"))
      (node (ref "R22") (pin "2") (pinfunction "2_2") (pintype "passive"))
      (node (ref "R26") (pin "2") (pinfunction "2_2") (pintype "passive"))
      (node (ref "R30") (pin "2") (pinfunction "2_2") (pintype "passive"))
      (node (ref "R31") (pin "2") (pinfunction "2_2") (pintype "passive"))
      (node (ref "R_FILTER1") (pin "1") (pinfunction "1_1") (pintype "passive"))
      (node (ref "U4") (pin "2") (pinfunction "COM_2") (pintype "passive"))
      (node (ref "U5") (pin "2") (pinfunction "COM_2") (pintype "passive"))
      (node (ref "U6") (pin "2") (pinfunction "COM_2") (pintype "passive"))
    )
    (net (code "4") (name "A_H") (class "Default")
      (node (ref "R12") (pin "2") (pinfunction "2_2") (pintype "passive"))
      (node (ref "U2") (pin "13") (pinfunction "PB1_13") (pintype "bidirectional"))
    )
    (net (code "5") (name "A_L") (class "Default")
      (node (ref "R13") (pin "2") (pinfunction "2_2") (pintype "passive"))
      (node (ref "U2") (pin "12") (pinfunction "PB0_12") (pintype "bidirectional"))
    )
    (net (code "6") (name "B_H") (class "Default")
      (node (ref "ICSP") (pin "4") (pinfunction "MOSI_4") (pintype "passive"))
      (node (ref "R3") (pin "2") (pinfunction "2_2") (pintype "passive"))
      (node (ref "U2") (pin "15") (pinfunction "PB3_15") (pintype "bidirectional"))
    )
    (net (code "7") (name "B_L") (class "Default")
      (node (ref "R11") (pin "2") (pinfunction "2_2") (pintype "passive"))
      (node (ref "U2") (pin "14") (pinfunction "PB2_14") (pintype "bidirectional"))
    )
    (net (code "8") (name "C_H") (class "Default")
      (node (ref "ICSP") (pin "5") (pinfunction "SCK_5") (pintype "passive"))
      (node (ref "R1") (pin "2") (pinfunction "2_2") (pintype "passive"))
      (node (ref "R10") (pin "1") (pinfunction "1_1") (pintype "passive"))
      (node (ref "U2") (pin "17") (pinfunction "PB5_17") (pintype "bidirectional"))
    )
    (net (code "9") (name "C_L") (class "Default")
      (node (ref "ICSP") (pin "6") (pinfunction "MISO_6") (pintype "passive"))
      (node (ref "R2") (pin "2") (pinfunction "2_2") (pintype "passive"))
      (node (ref "U2") (pin "16") (pinfunction "PB4_16") (pintype "bidirectional"))
    )
    (net (code "10") (name "DIR") (class "Default")
      (node (ref "RR1") (pin "2") (pinfunction "2_2") (pintype "passive"))
      (node (ref "RR8") (pin "1") (pinfunction "1_1") (pintype "passive"))
      (node (ref "U2") (pin "25") (pinfunction "PC2_25") (pintype "bidirectional"))
    )
    (net (code "11") (name "GND") (class "Default")
      (node (ref "C1") (pin "2") (pinfunction "2_2") (pintype "passive"))
      (node (ref "C10") (pin "2") (pinfunction "2_2") (pintype "passive"))
      (node (ref "C11") (pin "2") (pinfunction "2_2") (pintype "passive"))
      (node (ref "C12") (pin "2") (pinfunction "2_2") (pintype "passive"))
      (node (ref "C2") (pin "2") (pinfunction "2_2") (pintype "passive"))
      (node (ref "C4") (pin "2") (pinfunction "2_2") (pintype "passive"))
      (node (ref "C5") (pin "2") (pinfunction "2_2") (pintype "passive"))
      (node (ref "C6") (pin "-") (pinfunction "-_-") (pintype "passive"))
      (node (ref "C7") (pin "2") (pinfunction "2_2") (pintype "passive"))
      (node (ref "C8") (pin "-") (pinfunction "-_-") (pintype "passive"))
      (node (ref "C9") (pin "2") (pinfunction "2_2") (pintype "passive"))
      (node (ref "COMM") (pin "3") (pinfunction "3_3") (pintype "passive"))
      (node (ref "C_FILTER") (pin "2") (pinfunction "2_2") (pintype "passive"))
      (node (ref "C_FILTER1") (pin "2") (pinfunction "2_2") (pintype "passive"))
      (node (ref "DIRECTION") (pin "2") (pinfunction "KL_2") (pintype "passive"))
      (node (ref "FDTI") (pin "6") (pinfunction "GND_6") (pintype "passive"))
      (node (ref "HS_BYPASS_CAP") (pin "2") (pinfunction "2_2") (pintype "passive"))
      (node (ref "H_SENSOR") (pin "2") (pinfunction "KL_2") (pintype "passive"))
      (node (ref "IC1") (pin "2") (pinfunction "GND_2") (pintype "passive"))
      (node (ref "ICSP") (pin "2") (pinfunction "GND_2") (pintype "passive"))
      (node (ref "IR2110_I/P_BYPASS_CAP_A") (pin "2") (pinfunction "2_2") (pintype "passive"))
      (node (ref "IR2110_I/P_BYPASS_CAP_B") (pin "2") (pinfunction "2_2") (pintype "passive"))
      (node (ref "IR2110_I/P_BYPASS_CAP_C") (pin "2") (pinfunction "2_2") (pintype "passive"))
      (node (ref "LED1") (pin "C") (pinfunction "C_C") (pintype "passive"))
      (node (ref "LED2") (pin "C") (pinfunction "C_C") (pintype "passive"))
      (node (ref "MCU_BYPASS_CAP") (pin "2") (pinfunction "2_2") (pintype "passive"))
      (node (ref "MONITORBYPASSCAP") (pin "2") (pinfunction "2_2") (pintype "passive"))
      (node (ref "R14") (pin "2") (pinfunction "2_2") (pintype "passive"))
      (node (ref "R15") (pin "2") (pinfunction "2_2") (pintype "passive"))
      (node (ref "R16") (pin "2") (pinfunction "2_2") (pintype "passive"))
      (node (ref "R18") (pin "2") (pinfunction "2_2") (pintype "passive"))
      (node (ref "R31") (pin "1") (pinfunction "1_1") (pintype "passive"))
      (node (ref "R4") (pin "2") (pinfunction "2_2") (pintype "passive"))
      (node (ref "R5") (pin "2") (pinfunction "2_2") (pintype "passive"))
      (node (ref "R6") (pin "2") (pinfunction "2_2") (pintype "passive"))
      (node (ref "R7") (pin "2") (pinfunction "2_2") (pintype "passive"))
      (node (ref "R_ADJ") (pin "1") (pinfunction "1_1") (pintype "passive"))
      (node (ref "R_FILTER2") (pin "1") (pinfunction "1_1") (pintype "passive"))
      (node (ref "R_FILTER4") (pin "1") (pinfunction "1_1") (pintype "passive"))
      (node (ref "TB3") (pin "1_") (pinfunction "2_1_") (pintype "passive"))
      (node (ref "TC4468_BYPASS_CERACAP") (pin "2") (pinfunction "2_2") (pintype "passive"))
      (node (ref "TC4468_BYPASS_CERACAP1") (pin "2") (pinfunction "2_2") (pintype "passive"))
      (node (ref "TC4468_BYPASS_FILMCAP") (pin "2") (pinfunction "2_2") (pintype "passive"))
      (node (ref "TC4468_BYPASS_FILMCAP1") (pin "2") (pinfunction "2_2") (pintype "passive"))
      (node (ref "THROTTLE") (pin "2") (pinfunction "KL_2") (pintype "passive"))
      (node (ref "THROTTLE_BYPASS_CAP") (pin "2") (pinfunction "2_2") (pintype "passive"))
      (node (ref "U1") (pin "10") (pinfunction "4B_10") (pintype "input"))
      (node (ref "U1") (pin "7") (pinfunction "GND_7") (pintype "passive"))
      (node (ref "U1") (pin "9") (pinfunction "4A_9") (pintype "input"))
      (node (ref "U2") (pin "21") (pinfunction "GND_21") (pintype "passive"))
      (node (ref "U3") (pin "10") (pinfunction "4B_10") (pintype "input"))
      (node (ref "U3") (pin "7") (pinfunction "GND_7") (pintype "passive"))
      (node (ref "U3") (pin "9") (pinfunction "4A_9") (pintype "input"))
      (node (ref "U4") (pin "13") (pinfunction "SD_13") (pintype "input"))
      (node (ref "U4") (pin "15") (pinfunction "VSS_15") (pintype "passive"))
      (node (ref "U5") (pin "13") (pinfunction "SD_13") (pintype "input"))
      (node (ref "U5") (pin "15") (pinfunction "VSS_15") (pintype "passive"))
      (node (ref "U6") (pin "13") (pinfunction "SD_13") (pintype "input"))
      (node (ref "U6") (pin "15") (pinfunction "VSS_15") (pintype "passive"))
      (node (ref "U7") (pin "2") (pinfunction "GND_2") (pintype "passive"))
    )
    (net (code "12") (name "HIGH_DRIVE_A") (class "Default")
      (node (ref "D8") (pin "C") (pinfunction "C_C") (pintype "passive"))
      (node (ref "R27") (pin "2") (pinfunction "2_2") (pintype "passive"))
      (node (ref "U6") (pin "8") (pinfunction "HO_8") (pintype "output"))
    )
    (net (code "13") (name "HIGH_DRIVE_B") (class "Default")
      (node (ref "D6") (pin "C") (pinfunction "C_C") (pintype "passive"))
      (node (ref "R23") (pin "2") (pinfunction "2_2") (pintype "passive"))
      (node (ref "U5") (pin "8") (pinfunction "HO_8") (pintype "output"))
    )
    (net (code "14") (name "HIGH_DRIVE_C") (class "Default")
      (node (ref "D4") (pin "C") (pinfunction "C_C") (pintype "passive"))
      (node (ref "R19") (pin "2") (pinfunction "2_2") (pintype "passive"))
      (node (ref "U4") (pin "8") (pinfunction "HO_8") (pintype "output"))
    )
    (net (code "15") (name "HIN_A") (class "Default")
      (node (ref "U3") (pin "13") (pinfunction "2Y_13") (pintype "output"))
      (node (ref "U6") (pin "12") (pinfunction "HIN_12") (pintype "input"))
    )
    (net (code "16") (name "HIN_B") (class "Default")
      (node (ref "U1") (pin "12") (pinfunction "3Y_12") (pintype "output"))
      (node (ref "U5") (pin "12") (pinfunction "HIN_12") (pintype "input"))
    )
    (net (code "17") (name "HIN_C") (class "Default")
      (node (ref "U1") (pin "14") (pinfunction "1Y_14") (pintype "output"))
      (node (ref "U4") (pin "12") (pinfunction "HIN_12") (pintype "input"))
    )
    (net (code "18") (name "HS_A") (class "Default")
      (node (ref "C12") (pin "1") (pinfunction "1_1") (pintype "passive"))
      (node (ref "R_ADJ4") (pin "1") (pinfunction "1_1") (pintype "passive"))
      (node (ref "R_ADJ7") (pin "2") (pinfunction "2_2") (pintype "passive"))
      (node (ref "U2") (pin "2") (pinfunction "PD4_2") (pintype "bidirectional"))
    )
    (net (code "19") (name "HS_B") (class "Default")
      (node (ref "C11") (pin "1") (pinfunction "1_1") (pintype "passive"))
      (node (ref "R_ADJ3") (pin "1") (pinfunction "1_1") (pintype "passive"))
      (node (ref "R_ADJ6") (pin "2") (pinfunction "2_2") (pintype "passive"))
      (node (ref "U2") (pin "9") (pinfunction "PD5_9") (pintype "bidirectional"))
    )
    (net (code "20") (name "HS_C") (class "Default")
      (node (ref "C10") (pin "1") (pinfunction "1_1") (pintype "passive"))
      (node (ref "R_ADJ2") (pin "1") (pinfunction "1_1") (pintype "passive"))
      (node (ref "R_ADJ5") (pin "2") (pinfunction "2_2") (pintype "passive"))
      (node (ref "U2") (pin "10") (pinfunction "PD6_10") (pintype "bidirectional"))
    )
    (net (code "21") (name "LIN_A") (class "Default")
      (node (ref "U3") (pin "12") (pinfunction "3Y_12") (pintype "output"))
      (node (ref "U6") (pin "14") (pinfunction "LIN_14") (pintype "input"))
    )
    (net (code "22") (name "LIN_B") (class "Default")
      (node (ref "U3") (pin "14") (pinfunction "1Y_14") (pintype "output"))
      (node (ref "U5") (pin "14") (pinfunction "LIN_14") (pintype "input"))
    )
    (net (code "23") (name "LIN_C") (class "Default")
      (node (ref "U1") (pin "13") (pinfunction "2Y_13") (pintype "output"))
      (node (ref "U4") (pin "14") (pinfunction "LIN_14") (pintype "input"))
    )
    (net (code "24") (name "LOW_DRIVE_A") (class "Default")
      (node (ref "D9") (pin "C") (pinfunction "C_C") (pintype "passive"))
      (node (ref "R28") (pin "2") (pinfunction "2_2") (pintype "passive"))
      (node (ref "U6") (pin "1") (pinfunction "LO_1") (pintype "output"))
    )
    (net (code "25") (name "LOW_DRIVE_B") (class "Default")
      (node (ref "D7") (pin "C") (pinfunction "C_C") (pintype "passive"))
      (node (ref "R24") (pin "2") (pinfunction "2_2") (pintype "passive"))
      (node (ref "U5") (pin "1") (pinfunction "LO_1") (pintype "output"))
    )
    (net (code "26") (name "LOW_DRIVE_C") (class "Default")
      (node (ref "D5") (pin "C") (pinfunction "C_C") (pintype "passive"))
      (node (ref "R20") (pin "2") (pinfunction "2_2") (pintype "passive"))
      (node (ref "U4") (pin "1") (pinfunction "LO_1") (pintype "output"))
    )
    (net (code "27") (name "Net-(BRAKESA-KL)") (class "Default")
      (node (ref "BRAKES") (pin "1") (pinfunction "KL_1") (pintype "passive"))
      (node (ref "U2") (pin "32") (pinfunction "PD2_32") (pintype "bidirectional"))
    )
    (net (code "28") (name "Net-(C4-Pad1)") (class "Default")
      (node (ref "C4") (pin "1") (pinfunction "1_1") (pintype "passive"))
      (node (ref "R32") (pin "1") (pinfunction "1_1") (pintype "passive"))
      (node (ref "U8") (pin "IN") (pinfunction "IN_IN") (pintype "input"))
    )
    (net (code "29") (name "Net-(DIRECTIONA-KL)") (class "Default")
      (node (ref "DIRECTION") (pin "1") (pinfunction "KL_1") (pintype "passive"))
      (node (ref "RR1") (pin "1") (pinfunction "1_1") (pintype "passive"))
    )
    (net (code "30") (name "Net-(FDTI-DTR)") (class "Default")
      (node (ref "C3") (pin "1") (pinfunction "1_1") (pintype "passive"))
      (node (ref "FDTI") (pin "1") (pinfunction "DTR_1") (pintype "passive"))
    )
    (net (code "31") (name "Net-(FDTI-RXI)") (class "Default")
      (node (ref "COMM") (pin "1") (pinfunction "1_1") (pintype "passive"))
      (node (ref "FDTI") (pin "2") (pinfunction "RXI_2") (pintype "passive"))
      (node (ref "U2") (pin "31") (pinfunction "PD1_31") (pintype "bidirectional"))
    )
    (net (code "32") (name "Net-(FDTI-TXO)") (class "Default")
      (node (ref "COMM") (pin "2") (pinfunction "2_2") (pintype "passive"))
      (node (ref "FDTI") (pin "3") (pinfunction "TXO_3") (pintype "passive"))
      (node (ref "U2") (pin "30") (pinfunction "PD0_30") (pintype "bidirectional"))
    )
    (net (code "33") (name "Net-(H_SENSORC-KL)") (class "Default")
      (node (ref "H_SENSOR") (pin "3") (pinfunction "KL_3") (pintype "passive"))
      (node (ref "R_ADJ5") (pin "1") (pinfunction "1_1") (pintype "passive"))
    )
    (net (code "34") (name "Net-(H_SENSORD-KL)") (class "Default")
      (node (ref "H_SENSOR") (pin "4") (pinfunction "KL_4") (pintype "passive"))
      (node (ref "R_ADJ6") (pin "1") (pinfunction "1_1") (pintype "passive"))
    )
    (net (code "35") (name "Net-(H_SENSORE-KL)") (class "Default")
      (node (ref "H_SENSOR") (pin "5") (pinfunction "KL_5") (pintype "passive"))
      (node (ref "R_ADJ7") (pin "1") (pinfunction "1_1") (pintype "passive"))
    )
    (net (code "36") (name "Net-(ICSP-RST)") (class "Default")
      (node (ref "C3") (pin "2") (pinfunction "2_2") (pintype "passive"))
      (node (ref "ICSP") (pin "3") (pinfunction "RST_3") (pintype "passive"))
      (node (ref "U2") (pin "29") (pinfunction "PC6_29") (pintype "bidirectional"))
    )
    (net (code "37") (name "Net-(LED1-PadA)") (class "Default")
      (node (ref "LED1") (pin "A") (pinfunction "A_A") (pintype "passive"))
      (node (ref "R9") (pin "1") (pinfunction "1_1") (pintype "passive"))
    )
    (net (code "38") (name "Net-(LED2-PadA)") (class "Default")
      (node (ref "LED2") (pin "A") (pinfunction "A_A") (pintype "passive"))
      (node (ref "R10") (pin "2") (pinfunction "2_2") (pintype "passive"))
    )
    (net (code "39") (name "Net-(Q1-G)") (class "Default")
      (node (ref "D4") (pin "A") (pinfunction "A_A") (pintype "passive"))
      (node (ref "Q1") (pin "1") (pinfunction "G_1") (pintype "bidirectional"))
      (node (ref "R19") (pin "1") (pinfunction "1_1") (pintype "passive"))
      (node (ref "R21") (pin "1") (pinfunction "1_1") (pintype "passive"))
    )
    (net (code "40") (name "Net-(Q2-G)") (class "Default")
      (node (ref "D5") (pin "A") (pinfunction "A_A") (pintype "passive"))
      (node (ref "Q2") (pin "1") (pinfunction "G_1") (pintype "bidirectional"))
      (node (ref "R20") (pin "1") (pinfunction "1_1") (pintype "passive"))
      (node (ref "R22") (pin "1") (pinfunction "1_1") (pintype "passive"))
    )
    (net (code "41") (name "Net-(Q3-G)") (class "Default")
      (node (ref "D6") (pin "A") (pinfunction "A_A") (pintype "passive"))
      (node (ref "Q3") (pin "1") (pinfunction "G_1") (pintype "bidirectional"))
      (node (ref "R23") (pin "1") (pinfunction "1_1") (pintype "passive"))
      (node (ref "R25") (pin "1") (pinfunction "1_1") (pintype "passive"))
    )
    (net (code "42") (name "Net-(Q4-G)") (class "Default")
      (node (ref "D7") (pin "A") (pinfunction "A_A") (pintype "passive"))
      (node (ref "Q4") (pin "1") (pinfunction "G_1") (pintype "bidirectional"))
      (node (ref "R24") (pin "1") (pinfunction "1_1") (pintype "passive"))
      (node (ref "R26") (pin "1") (pinfunction "1_1") (pintype "passive"))
    )
    (net (code "43") (name "Net-(Q5-G)") (class "Default")
      (node (ref "D8") (pin "A") (pinfunction "A_A") (pintype "passive"))
      (node (ref "Q5") (pin "1") (pinfunction "G_1") (pintype "bidirectional"))
      (node (ref "R27") (pin "1") (pinfunction "1_1") (pintype "passive"))
      (node (ref "R29") (pin "1") (pinfunction "1_1") (pintype "passive"))
    )
    (net (code "44") (name "Net-(Q6-G)") (class "Default")
      (node (ref "D9") (pin "A") (pinfunction "A_A") (pintype "passive"))
      (node (ref "Q6") (pin "1") (pinfunction "G_1") (pintype "bidirectional"))
      (node (ref "R28") (pin "1") (pinfunction "1_1") (pintype "passive"))
      (node (ref "R30") (pin "1") (pinfunction "1_1") (pintype "passive"))
    )
    (net (code "45") (name "Net-(R_ADJ-Pad2)") (class "Default")
      (node (ref "R_ADJ") (pin "2") (pinfunction "2_2") (pintype "passive"))
      (node (ref "R_ADJ1") (pin "1") (pinfunction "1_1") (pintype "passive"))
      (node (ref "U8") (pin "ADJ") (pinfunction "ADJ_ADJ") (pintype "input"))
    )
    (net (code "46") (name "Net-(THROTTLEC-KL)") (class "Default")
      (node (ref "THROTTLE") (pin "3") (pinfunction "KL_3") (pintype "passive"))
      (node (ref "U2") (pin "23") (pinfunction "PC0_23") (pintype "bidirectional"))
    )
    (net (code "47") (name "Net-(U1-1A)") (class "Default")
      (node (ref "R1") (pin "1") (pinfunction "1_1") (pintype "passive"))
      (node (ref "R4") (pin "1") (pinfunction "1_1") (pintype "passive"))
      (node (ref "U1") (pin "1") (pinfunction "1A_1") (pintype "input"))
    )
    (net (code "48") (name "Net-(U1-1B)") (class "Default")
      (node (ref "R7") (pin "1") (pinfunction "1_1") (pintype "passive"))
      (node (ref "R8") (pin "1") (pinfunction "1_1") (pintype "passive"))
      (node (ref "U1") (pin "2") (pinfunction "1B_2") (pintype "input"))
      (node (ref "U1") (pin "6") (pinfunction "3B_6") (pintype "input"))
    )
    (net (code "49") (name "Net-(U1-2A)") (class "Default")
      (node (ref "R2") (pin "1") (pinfunction "1_1") (pintype "passive"))
      (node (ref "R5") (pin "1") (pinfunction "1_1") (pintype "passive"))
      (node (ref "U1") (pin "3") (pinfunction "2A_3") (pintype "input"))
    )
    (net (code "50") (name "Net-(U1-3A)") (class "Default")
      (node (ref "R3") (pin "1") (pinfunction "1_1") (pintype "passive"))
      (node (ref "R6") (pin "1") (pinfunction "1_1") (pintype "passive"))
      (node (ref "U1") (pin "5") (pinfunction "3A_5") (pintype "input"))
    )
    (net (code "51") (name "Net-(U2-PB6)") (class "Default")
      (node (ref "C1") (pin "1") (pinfunction "1_1") (pintype "passive"))
      (node (ref "U2") (pin "7") (pinfunction "PB6_7") (pintype "bidirectional"))
      (node (ref "XTAL1") (pin "1") (pinfunction "1_1") (pintype "passive"))
    )
    (net (code "52") (name "Net-(U2-PB7)") (class "Default")
      (node (ref "C2") (pin "1") (pinfunction "1_1") (pintype "passive"))
      (node (ref "U2") (pin "8") (pinfunction "PB7_8") (pintype "bidirectional"))
      (node (ref "XTAL1") (pin "3") (pinfunction "3_3") (pintype "passive"))
    )
    (net (code "53") (name "Net-(U3-1A)") (class "Default")
      (node (ref "R11") (pin "1") (pinfunction "1_1") (pintype "passive"))
      (node (ref "R14") (pin "1") (pinfunction "1_1") (pintype "passive"))
      (node (ref "U3") (pin "1") (pinfunction "1A_1") (pintype "input"))
    )
    (net (code "54") (name "Net-(U3-2A)") (class "Default")
      (node (ref "R12") (pin "1") (pinfunction "1_1") (pintype "passive"))
      (node (ref "R15") (pin "1") (pinfunction "1_1") (pintype "passive"))
      (node (ref "U3") (pin "3") (pinfunction "2A_3") (pintype "input"))
    )
    (net (code "55") (name "Net-(U3-2B)") (class "Default")
      (node (ref "R17") (pin "1") (pinfunction "1_1") (pintype "passive"))
      (node (ref "R18") (pin "1") (pinfunction "1_1") (pintype "passive"))
      (node (ref "U3") (pin "4") (pinfunction "2B_4") (pintype "input"))
    )
    (net (code "56") (name "Net-(U3-3A)") (class "Default")
      (node (ref "R13") (pin "1") (pinfunction "1_1") (pintype "passive"))
      (node (ref "R16") (pin "1") (pinfunction "1_1") (pintype "passive"))
      (node (ref "U3") (pin "5") (pinfunction "3A_5") (pintype "input"))
    )
    (net (code "57") (name "Net-(U7-IN+)") (class "Default")
      (node (ref "C_FILTER") (pin "1") (pinfunction "1_1") (pintype "passive"))
      (node (ref "R_FILTER1") (pin "2") (pinfunction "2_2") (pintype "passive"))
      (node (ref "U7") (pin "4") (pinfunction "IN+_4") (pintype "input"))
    )
    (net (code "58") (name "Net-(U7-IN-)") (class "Default")
      (node (ref "C_FILTER1") (pin "1") (pinfunction "1_1") (pintype "passive"))
      (node (ref "R_FILTER2") (pin "2") (pinfunction "2_2") (pintype "passive"))
      (node (ref "U7") (pin "5") (pinfunction "IN-_5") (pintype "input"))
    )
    (net (code "59") (name "Net-(U7-REF)") (class "Default")
      (node (ref "R_FILTER3") (pin "2") (pinfunction "2_2") (pintype "passive"))
      (node (ref "R_FILTER4") (pin "2") (pinfunction "2_2") (pintype "passive"))
      (node (ref "U7") (pin "1") (pinfunction "REF_1") (pintype "input"))
    )
    (net (code "60") (name "OCP") (class "Default")
      (node (ref "U2") (pin "11") (pinfunction "PD7_11") (pintype "bidirectional"))
      (node (ref "U2") (pin "24") (pinfunction "PC1_24") (pintype "bidirectional"))
      (node (ref "U7") (pin "6") (pinfunction "OUT_6") (pintype "output"))
    )
    (net (code "61") (name "PWM") (class "Default")
      (node (ref "R17") (pin "2") (pinfunction "2_2") (pintype "passive"))
      (node (ref "R8") (pin "2") (pinfunction "2_2") (pintype "passive"))
      (node (ref "U2") (pin "1") (pinfunction "PD3_1") (pintype "bidirectional"))
    )
    (net (code "62") (name "VB_A") (class "Default")
      (node (ref "D2") (pin "C") (pinfunction "C_C") (pintype "passive"))
      (node (ref "IR2110_BOOTSTRAP_CAP_A") (pin "P$1") (pinfunction "1_P$1") (pintype "passive"))
      (node (ref "U6") (pin "7") (pinfunction "VB_7") (pintype "power_in"))
    )
    (net (code "63") (name "VB_B") (class "Default")
      (node (ref "D3") (pin "C") (pinfunction "C_C") (pintype "passive"))
      (node (ref "IR2110_BOOTSTRP_CAP_B") (pin "P$1") (pinfunction "1_P$1") (pintype "passive"))
      (node (ref "U5") (pin "7") (pinfunction "VB_7") (pintype "power_in"))
    )
    (net (code "64") (name "VB_C") (class "Default")
      (node (ref "D1") (pin "C") (pinfunction "C_C") (pintype "passive"))
      (node (ref "IR2110_BOOTSTRAP_CAP_C") (pin "P$1") (pinfunction "1_P$1") (pintype "passive"))
      (node (ref "U4") (pin "7") (pinfunction "VB_7") (pintype "power_in"))
    )
    (net (code "65") (name "VCC") (class "Default")
      (node (ref "BRAKES") (pin "2") (pinfunction "KL_2") (pintype "passive"))
      (node (ref "C9") (pin "1") (pinfunction "1_1") (pintype "passive"))
      (node (ref "FDTI") (pin "4") (pinfunction "VCC_4") (pintype "passive"))
      (node (ref "HS_BYPASS_CAP") (pin "1") (pinfunction "1_1") (pintype "passive"))
      (node (ref "H_SENSOR") (pin "1") (pinfunction "KL_1") (pintype "passive"))
      (node (ref "IC1") (pin "3") (pinfunction "VO_3") (pintype "passive"))
      (node (ref "ICSP") (pin "1") (pinfunction "VCC_1") (pintype "passive"))
      (node (ref "MCU_BYPASS_CAP") (pin "1") (pinfunction "1_1") (pintype "passive"))
      (node (ref "MONITORBYPASSCAP") (pin "1") (pinfunction "1_1") (pintype "passive"))
      (node (ref "R9") (pin "2") (pinfunction "2_2") (pintype "passive"))
      (node (ref "RR8") (pin "2") (pinfunction "2_2") (pintype "passive"))
      (node (ref "R_ADJ2") (pin "2") (pinfunction "2_2") (pintype "passive"))
      (node (ref "R_ADJ3") (pin "2") (pinfunction "2_2") (pintype "passive"))
      (node (ref "R_ADJ4") (pin "2") (pinfunction "2_2") (pintype "passive"))
      (node (ref "R_FILTER3") (pin "1") (pinfunction "1_1") (pintype "passive"))
      (node (ref "THROTTLE") (pin "1") (pinfunction "KL_1") (pintype "passive"))
      (node (ref "THROTTLE_BYPASS_CAP") (pin "1") (pinfunction "1_1") (pintype "passive"))
      (node (ref "U2") (pin "18") (pinfunction "AVCC_18") (pintype "power_in"))
      (node (ref "U2") (pin "4") (pinfunction "VCC_2_4") (pintype "power_in"))
      (node (ref "U2") (pin "6") (pinfunction "VCC_6") (pintype "power_in"))
      (node (ref "U7") (pin "3") (pinfunction "V+_3") (pintype "power_in"))
    )
    (net (code "66") (name "VS_A") (class "Default")
      (node (ref "IR2110_BOOTSTRAP_CAP_A") (pin "P$2") (pinfunction "2_P$2") (pintype "passive"))
      (node (ref "Q5") (pin "3") (pinfunction "S_3") (pintype "bidirectional"))
      (node (ref "Q6") (pin "2") (pinfunction "D_2") (pintype "bidirectional"))
      (node (ref "R29") (pin "2") (pinfunction "2_2") (pintype "passive"))
      (node (ref "TB1") (pin "3_") (pinfunction "6_3_") (pintype "passive"))
      (node (ref "U6") (pin "6") (pinfunction "VS_6") (pintype "power_in"))
    )
    (net (code "67") (name "VS_B") (class "Default")
      (node (ref "IR2110_BOOTSTRP_CAP_B") (pin "P$2") (pinfunction "2_P$2") (pintype "passive"))
      (node (ref "Q3") (pin "3") (pinfunction "S_3") (pintype "bidirectional"))
      (node (ref "Q4") (pin "2") (pinfunction "D_2") (pintype "bidirectional"))
      (node (ref "R25") (pin "2") (pinfunction "2_2") (pintype "passive"))
      (node (ref "TB1") (pin "2_") (pinfunction "4_2_") (pintype "passive"))
      (node (ref "U5") (pin "6") (pinfunction "VS_6") (pintype "power_in"))
    )
    (net (code "68") (name "VS_C") (class "Default")
      (node (ref "IR2110_BOOTSTRAP_CAP_C") (pin "P$2") (pinfunction "2_P$2") (pintype "passive"))
      (node (ref "Q1") (pin "3") (pinfunction "S_3") (pintype "bidirectional"))
      (node (ref "Q2") (pin "2") (pinfunction "D_2") (pintype "bidirectional"))
      (node (ref "R21") (pin "2") (pinfunction "2_2") (pintype "passive"))
      (node (ref "TB1") (pin "1_") (pinfunction "2_1_") (pintype "passive"))
      (node (ref "U4") (pin "6") (pinfunction "VS_6") (pintype "power_in"))
    )
    (net (code "69") (name "unconnected-(FDTI-CTS-Pad5)") (class "Default")
      (node (ref "FDTI") (pin "5") (pinfunction "CTS_5") (pintype "passive"))
    )
    (net (code "70") (name "unconnected-(KK1-K-PadA2,5)") (class "Default")
      (node (ref "KK1") (pin "A2,5") (pinfunction "K_A2,5") (pintype "passive"))
    )
    (net (code "71") (name "unconnected-(KK1-K-PadB2,5)") (class "Default")
      (node (ref "KK1") (pin "B2,5") (pinfunction "K_B2,5") (pintype "passive"))
    )
    (net (code "72") (name "unconnected-(KK2-K-PadA2,5)") (class "Default")
      (node (ref "KK2") (pin "A2,5") (pinfunction "K_A2,5") (pintype "passive"))
    )
    (net (code "73") (name "unconnected-(KK2-K-PadB2,5)") (class "Default")
      (node (ref "KK2") (pin "B2,5") (pinfunction "K_B2,5") (pintype "passive"))
    )
    (net (code "74") (name "unconnected-(KK3-K-PadA2,5)") (class "Default")
      (node (ref "KK3") (pin "A2,5") (pinfunction "K_A2,5") (pintype "passive"))
    )
    (net (code "75") (name "unconnected-(KK3-K-PadB2,5)") (class "Default")
      (node (ref "KK3") (pin "B2,5") (pinfunction "K_B2,5") (pintype "passive"))
    )
    (net (code "76") (name "unconnected-(KK4-K-PadA2,5)") (class "Default")
      (node (ref "KK4") (pin "A2,5") (pinfunction "K_A2,5") (pintype "passive"))
    )
    (net (code "77") (name "unconnected-(KK4-K-PadB2,5)") (class "Default")
      (node (ref "KK4") (pin "B2,5") (pinfunction "K_B2,5") (pintype "passive"))
    )
    (net (code "78") (name "unconnected-(KK5-K-PadA2,5)") (class "Default")
      (node (ref "KK5") (pin "A2,5") (pinfunction "K_A2,5") (pintype "passive"))
    )
    (net (code "79") (name "unconnected-(KK5-K-PadB2,5)") (class "Default")
      (node (ref "KK5") (pin "B2,5") (pinfunction "K_B2,5") (pintype "passive"))
    )
    (net (code "80") (name "unconnected-(KK6-K-PadA2,5)") (class "Default")
      (node (ref "KK6") (pin "A2,5") (pinfunction "K_A2,5") (pintype "passive"))
    )
    (net (code "81") (name "unconnected-(KK6-K-PadB2,5)") (class "Default")
      (node (ref "KK6") (pin "B2,5") (pinfunction "K_B2,5") (pintype "passive"))
    )
    (net (code "82") (name "unconnected-(TB1-3-Pad2)") (class "Default")
      (node (ref "TB1") (pin "2") (pinfunction "3_2") (pintype "passive"))
    )
    (net (code "83") (name "unconnected-(TB1-5-Pad3)") (class "Default")
      (node (ref "TB1") (pin "3") (pinfunction "5_3") (pintype "passive"))
    )
    (net (code "84") (name "unconnected-(TB1-Pad1)") (class "Default")
      (node (ref "TB1") (pin "1") (pinfunction "1_1") (pintype "passive"))
    )
    (net (code "85") (name "unconnected-(TB3-3-Pad2)") (class "Default")
      (node (ref "TB3") (pin "2") (pinfunction "3_2") (pintype "passive"))
    )
    (net (code "86") (name "unconnected-(TB3-4-Pad2_)") (class "Default")
      (node (ref "TB3") (pin "2_") (pinfunction "4_2_") (pintype "passive"))
    )
    (net (code "87") (name "unconnected-(TB3-5-Pad3)") (class "Default")
      (node (ref "TB3") (pin "3") (pinfunction "5_3") (pintype "passive"))
    )
    (net (code "88") (name "unconnected-(TB3-Pad1)") (class "Default")
      (node (ref "TB3") (pin "1") (pinfunction "1_1") (pintype "passive"))
    )
    (net (code "89") (name "unconnected-(U1-4Y-Pad11)") (class "Default")
      (node (ref "U1") (pin "11") (pinfunction "4Y_11") (pintype "output"))
    )
    (net (code "90") (name "unconnected-(U1-GND_2-Pad8)") (class "Default")
      (node (ref "U1") (pin "8") (pinfunction "GND_2_8") (pintype "passive"))
    )
    (net (code "91") (name "unconnected-(U2-ADC6-Pad19)") (class "Default")
      (node (ref "U2") (pin "19") (pinfunction "ADC6_19") (pintype "input"))
    )
    (net (code "92") (name "unconnected-(U2-ADC7-Pad22)") (class "Default")
      (node (ref "U2") (pin "22") (pinfunction "ADC7_22") (pintype "input"))
    )
    (net (code "93") (name "unconnected-(U2-AREF-Pad20)") (class "Default")
      (node (ref "U2") (pin "20") (pinfunction "AREF_20") (pintype "input"))
    )
    (net (code "94") (name "unconnected-(U2-GND_2-Pad3)") (class "Default")
      (node (ref "U2") (pin "3") (pinfunction "GND_2_3") (pintype "passive"))
    )
    (net (code "95") (name "unconnected-(U2-GND_3-Pad5)") (class "Default")
      (node (ref "U2") (pin "5") (pinfunction "GND_3_5") (pintype "passive"))
    )
    (net (code "96") (name "unconnected-(U2-PC3-Pad26)") (class "Default")
      (node (ref "U2") (pin "26") (pinfunction "PC3_26") (pintype "bidirectional"))
    )
    (net (code "97") (name "unconnected-(U2-PC4-Pad27)") (class "Default")
      (node (ref "U2") (pin "27") (pinfunction "PC4_27") (pintype "bidirectional"))
    )
    (net (code "98") (name "unconnected-(U2-PC5-Pad28)") (class "Default")
      (node (ref "U2") (pin "28") (pinfunction "PC5_28") (pintype "bidirectional"))
    )
    (net (code "99") (name "unconnected-(U3-4Y-Pad11)") (class "Default")
      (node (ref "U3") (pin "11") (pinfunction "4Y_11") (pintype "output"))
    )
    (net (code "100") (name "unconnected-(U3-GND_2-Pad8)") (class "Default")
      (node (ref "U3") (pin "8") (pinfunction "GND_2_8") (pintype "passive"))
    )
    (net (code "101") (name "unconnected-(U4-NC-Pad10)") (class "Default")
      (node (ref "U4") (pin "10") (pinfunction "NC_10") (pintype "no_connect"))
    )
    (net (code "102") (name "unconnected-(U4-NC_2-Pad4)") (class "Default")
      (node (ref "U4") (pin "4") (pinfunction "NC_2_4") (pintype "no_connect"))
    )
    (net (code "103") (name "unconnected-(U4-NC_3-Pad5)") (class "Default")
      (node (ref "U4") (pin "5") (pinfunction "NC_3_5") (pintype "no_connect"))
    )
    (net (code "104") (name "unconnected-(U4-NC_4-Pad9)") (class "Default")
      (node (ref "U4") (pin "9") (pinfunction "NC_4_9") (pintype "no_connect"))
    )
    (net (code "105") (name "unconnected-(U4-NC_5-Pad16)") (class "Default")
      (node (ref "U4") (pin "16") (pinfunction "NC_5_16") (pintype "no_connect"))
    )
    (net (code "106") (name "unconnected-(U5-NC-Pad10)") (class "Default")
      (node (ref "U5") (pin "10") (pinfunction "NC_10") (pintype "no_connect"))
    )
    (net (code "107") (name "unconnected-(U5-NC_2-Pad4)") (class "Default")
      (node (ref "U5") (pin "4") (pinfunction "NC_2_4") (pintype "no_connect"))
    )
    (net (code "108") (name "unconnected-(U5-NC_3-Pad5)") (class "Default")
      (node (ref "U5") (pin "5") (pinfunction "NC_3_5") (pintype "no_connect"))
    )
    (net (code "109") (name "unconnected-(U5-NC_4-Pad9)") (class "Default")
      (node (ref "U5") (pin "9") (pinfunction "NC_4_9") (pintype "no_connect"))
    )
    (net (code "110") (name "unconnected-(U5-NC_5-Pad16)") (class "Default")
      (node (ref "U5") (pin "16") (pinfunction "NC_5_16") (pintype "no_connect"))
    )
    (net (code "111") (name "unconnected-(U6-NC-Pad10)") (class "Default")
      (node (ref "U6") (pin "10") (pinfunction "NC_10") (pintype "no_connect"))
    )
    (net (code "112") (name "unconnected-(U6-NC_2-Pad4)") (class "Default")
      (node (ref "U6") (pin "4") (pinfunction "NC_2_4") (pintype "no_connect"))
    )
    (net (code "113") (name "unconnected-(U6-NC_3-Pad5)") (class "Default")
      (node (ref "U6") (pin "5") (pinfunction "NC_3_5") (pintype "no_connect"))
    )
    (net (code "114") (name "unconnected-(U6-NC_4-Pad9)") (class "Default")
      (node (ref "U6") (pin "9") (pinfunction "NC_4_9") (pintype "no_connect"))
    )
    (net (code "115") (name "unconnected-(U6-NC_5-Pad16)") (class "Default")
      (node (ref "U6") (pin "16") (pinfunction "NC_5_16") (pintype "no_connect"))
    )
  )
)
